# Power_Dist.net
KiCad netlist of a schematic drawn in Altium Designer
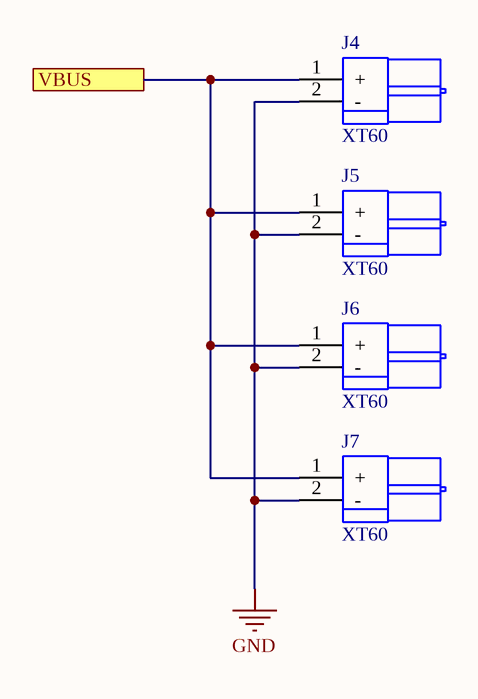
[diagram p0: Power_Dist.SchDoc]

(export (version "E")
  (design (tool "Eeschema 10.0.6"))
  (components
    (comp (ref "J4")
      (value "XT60")
      (footprint "J_XT60_Thru_Female")
      (description "60 Amp XT60 Connector")
      (libsource (lib "connector") (part "J_XT60"))
    )
    (comp (ref "J5")
      (value "XT60")
      (footprint "J_XT60_Thru_Female")
      (description "60 Amp XT60 Connector")
      (libsource (lib "connector") (part "J_XT60"))
    )
    (comp (ref "J6")
      (value "XT60")
      (footprint "J_XT60_Thru_Female")
      (description "60 Amp XT60 Connector")
      (libsource (lib "connector") (part "J_XT60"))
    )
    (comp (ref "J7")
      (value "XT60")
      (footprint "J_XT60_Thru_Female")
      (description "60 Amp XT60 Connector")
      (libsource (lib "connector") (part "J_XT60"))
    )
  )
  (nets
    (net (code "1") (name "/VBUS") (class "Default")
      (node (ref "J4") (pin "1") (pinfunction "+_1") (pintype "passive"))
      (node (ref "J5") (pin "1") (pinfunction "+_1") (pintype "passive"))
      (node (ref "J6") (pin "1") (pinfunction "+_1") (pintype "passive"))
      (node (ref "J7") (pin "1") (pinfunction "+_1") (pintype "passive"))
    )
    (net (code "2") (name "GND") (class "Default")
      (node (ref "J4") (pin "2") (pinfunction "-_2") (pintype "passive"))
      (node (ref "J5") (pin "2") (pinfunction "-_2") (pintype "passive"))
      (node (ref "J6") (pin "2") (pinfunction "-_2") (pintype "passive"))
      (node (ref "J7") (pin "2") (pinfunction "-_2") (pintype "passive"))
    )
  )
)
